# 02__RF_Power.net
KiCad netlist of a schematic drawn in Altium Designer
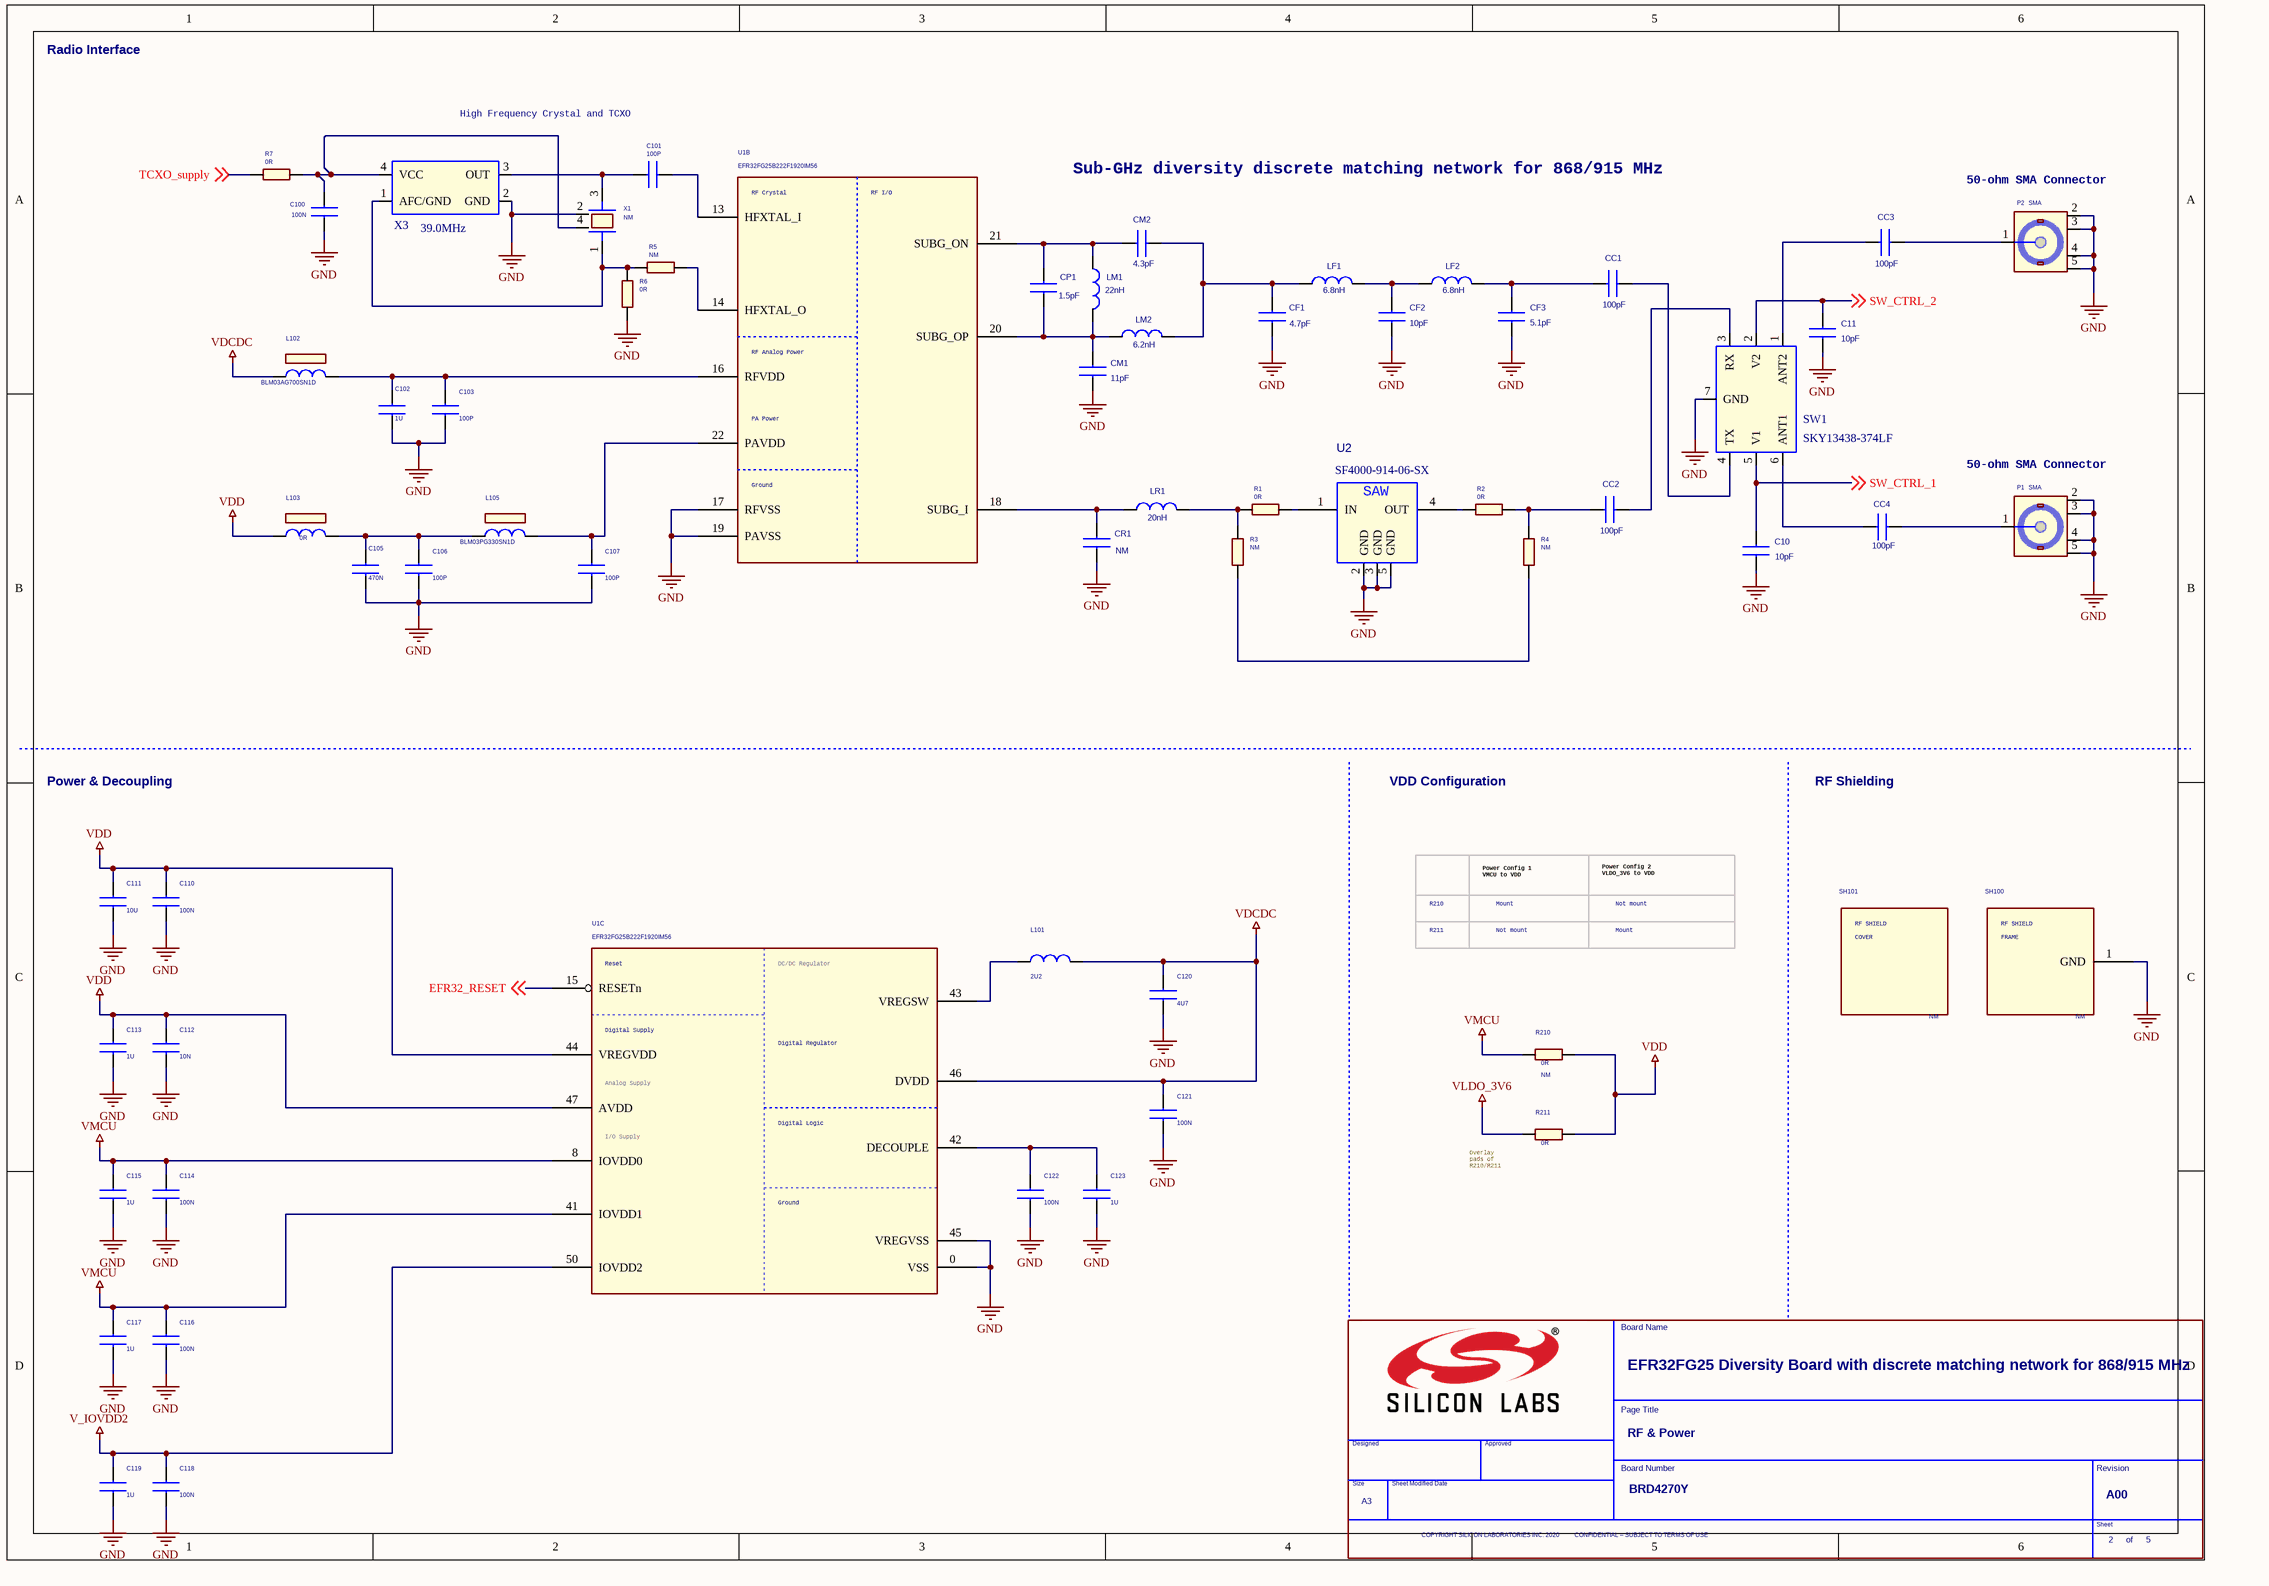
[diagram p0: 02_ RF & Power.SchDoc]

(export (version "E")
  (design (tool "Eeschema 10.0.6"))
  (components
    (comp (ref "C10")
      (value "10pF")
      (footprint "C0201_L")
      (fields (field (name "TOLERANCE") "±0.05P") (field (name "MFG") "Murata"))
      (libsource (lib "*") (part "C0201"))
    )
    (comp (ref "C11")
      (value "10pF")
      (footprint "C0201_L")
      (fields (field (name "TOLERANCE") "±0.05P") (field (name "MFG") "Murata"))
      (libsource (lib "*") (part "C0201"))
    )
    (comp (ref "C100")
      (value "100N")
      (footprint "C0201_L")
      (fields (field (name "TOLERANCE") "20%"))
      (libsource (lib "*") (part "C0201"))
    )
    (comp (ref "C101")
      (value "100P")
      (footprint "C0201_L")
      (fields (field (name "TOLERANCE") "5%"))
      (libsource (lib "*") (part "C0201"))
    )
    (comp (ref "C102")
      (value "1U")
      (footprint "C0402_L")
      (fields (field (name "TOLERANCE") "10%"))
      (libsource (lib "*") (part "C0402"))
    )
    (comp (ref "C103")
      (value "100P")
      (footprint "C0201_L")
      (fields (field (name "TOLERANCE") "5%"))
      (libsource (lib "*") (part "C0201"))
    )
    (comp (ref "C105")
      (value "470N")
      (footprint "C0402_L")
      (fields (field (name "TOLERANCE") "10%"))
      (libsource (lib "*") (part "C0402"))
    )
    (comp (ref "C106")
      (value "100P")
      (footprint "C0201_L")
      (fields (field (name "TOLERANCE") "5%"))
      (libsource (lib "*") (part "C0201"))
    )
    (comp (ref "C107")
      (value "100P")
      (footprint "C0201_L")
      (fields (field (name "TOLERANCE") "5%"))
      (libsource (lib "*") (part "C0201"))
    )
    (comp (ref "C110")
      (value "100N")
      (footprint "C0201_L")
      (fields (field (name "TOLERANCE") "20%"))
      (libsource (lib "*") (part "C0201"))
    )
    (comp (ref "C111")
      (value "10U")
      (footprint "C0603_L")
      (fields (field (name "TOLERANCE") "20%"))
      (libsource (lib "*") (part "C0603"))
    )
    (comp (ref "C112")
      (value "10N")
      (footprint "C0201_L")
      (fields (field (name "TOLERANCE") "10%"))
      (libsource (lib "*") (part "C0201"))
    )
    (comp (ref "C113")
      (value "1U")
      (footprint "C0402_L")
      (fields (field (name "TOLERANCE") "10%"))
      (libsource (lib "*") (part "C0402"))
    )
    (comp (ref "C114")
      (value "100N")
      (footprint "C0201_L")
      (fields (field (name "TOLERANCE") "20%"))
      (libsource (lib "*") (part "C0201"))
    )
    (comp (ref "C115")
      (value "1U")
      (footprint "C0402_L")
      (fields (field (name "TOLERANCE") "10%"))
      (libsource (lib "*") (part "C0402"))
    )
    (comp (ref "C116")
      (value "100N")
      (footprint "C0201_L")
      (fields (field (name "TOLERANCE") "20%"))
      (libsource (lib "*") (part "C0201"))
    )
    (comp (ref "C117")
      (value "1U")
      (footprint "C0402_L")
      (fields (field (name "TOLERANCE") "10%"))
      (libsource (lib "*") (part "C0402"))
    )
    (comp (ref "C118")
      (value "100N")
      (footprint "C0201_L")
      (fields (field (name "TOLERANCE") "20%"))
      (libsource (lib "*") (part "C0201"))
    )
    (comp (ref "C119")
      (value "1U")
      (footprint "C0402_L")
      (fields (field (name "TOLERANCE") "10%"))
      (libsource (lib "*") (part "C0402"))
    )
    (comp (ref "C120")
      (value "4U7")
      (footprint "C0603_L")
      (fields (field (name "TOLERANCE") "10%"))
      (libsource (lib "*") (part "C0603"))
    )
    (comp (ref "C121")
      (value "100N")
      (footprint "C0201_L")
      (fields (field (name "TOLERANCE") "20%"))
      (libsource (lib "*") (part "C0201"))
    )
    (comp (ref "C122")
      (value "100N")
      (footprint "C0201_L")
      (fields (field (name "TOLERANCE") "20%"))
      (libsource (lib "*") (part "C0201"))
    )
    (comp (ref "C123")
      (value "1U")
      (footprint "C0402_L")
      (fields (field (name "TOLERANCE") "10%"))
      (libsource (lib "*") (part "C0402"))
    )
    (comp (ref "CC1")
      (value "100pF")
      (footprint "C0201_L")
      (fields (field (name "TOLERANCE") "±0.05P") (field (name "MFG") "Murata"))
      (libsource (lib "*") (part "C0201"))
    )
    (comp (ref "CC2")
      (value "100pF")
      (footprint "C0201_L")
      (fields (field (name "TOLERANCE") "±0.05P") (field (name "MFG") "Murata"))
      (libsource (lib "*") (part "C0201"))
    )
    (comp (ref "CC3")
      (value "100pF")
      (footprint "C0201_L")
      (fields (field (name "TOLERANCE") "±0.05P") (field (name "MFG") "Murata"))
      (libsource (lib "*") (part "C0201"))
    )
    (comp (ref "CC4")
      (value "100pF")
      (footprint "C0201_L")
      (fields (field (name "TOLERANCE") "±0.05P") (field (name "MFG") "Murata"))
      (libsource (lib "*") (part "C0201"))
    )
    (comp (ref "CF1")
      (value "4.7pF")
      (footprint "C0201_L")
      (fields (field (name "TOLERANCE") "±0.1P") (field (name "MFG") "Murata"))
      (libsource (lib "*") (part "C0201"))
    )
    (comp (ref "CF2")
      (value "10pF")
      (footprint "C0201_L")
      (fields (field (name "TOLERANCE") "±0.1P") (field (name "MFG") "Murata"))
      (libsource (lib "*") (part "C0201"))
    )
    (comp (ref "CF3")
      (value "5.1pF")
      (footprint "C0201_L")
      (fields (field (name "TOLERANCE") "±0.05P") (field (name "MFG") "Murata"))
      (libsource (lib "*") (part "C0201"))
    )
    (comp (ref "CM1")
      (value "11pF")
      (footprint "C0201_L")
      (fields (field (name "TOLERANCE") "±0.1P") (field (name "MFG") "Murata"))
      (libsource (lib "*") (part "C0201"))
    )
    (comp (ref "CM2")
      (value "4.3pF")
      (footprint "C0201_L")
      (fields (field (name "TOLERANCE") "±0.05P") (field (name "MFG") "Murata"))
      (libsource (lib "*") (part "C0201"))
    )
    (comp (ref "CP1")
      (value "1.5pF")
      (footprint "C0201_L")
      (fields (field (name "TOLERANCE") "±0.1P") (field (name "MFG") "Murata"))
      (libsource (lib "*") (part "C0201"))
    )
    (comp (ref "CR1")
      (value "Unused")
      (footprint "C0201_L")
      (fields
        (field (name "TOLERANCE") "±0.05P")
        (field (name "NOT MOUNTED") "NM")
        (field (name "MFG") "Murata")
      )
      (libsource (lib "*") (part "C0201"))
    )
    (comp (ref "L101")
      (value "2U2")
      (footprint "COIL_1008_L")
      (fields (field (name "MFG") "Murata") (field (name "TOLERANCE") "+/-20%"))
      (libsource (lib "*") (part "L1008"))
    )
    (comp (ref "L102")
      (value "BLM03AG700SN1D")
      (footprint "COIL_MUR_BLM03_0201")
      (fields (field (name "MFG") "Murata"))
      (libsource (lib "*") (part "BLM03AX"))
    )
    (comp (ref "L103") (value "0R") (footprint "COIL_MUR_BLM03_0201") (libsource (lib "*") (part "BLM03AX")))
    (comp (ref "L105")
      (value "BLM03PG330SN1D")
      (footprint "COIL_MUR_BLM03_0201")
      (fields (field (name "MFG") "Murata"))
      (libsource (lib "*") (part "BLM03AX"))
    )
    (comp (ref "LF1")
      (value "6.8nH")
      (footprint "COIL_0201_L")
      (fields (field (name "TOLERANCE") "±3%") (field (name "MFG") "Murata"))
      (libsource (lib "*") (part "L0201"))
    )
    (comp (ref "LF2")
      (value "6.8nH")
      (footprint "COIL_0201_L")
      (fields (field (name "TOLERANCE") "±3%") (field (name "MFG") "Murata"))
      (libsource (lib "*") (part "L0201"))
    )
    (comp (ref "LM1")
      (value "22nH")
      (footprint "COIL_0201_L")
      (fields (field (name "TOLERANCE") "±0.1N") (field (name "MFG") "Murata"))
      (libsource (lib "*") (part "L0201"))
    )
    (comp (ref "LM2") (value "6.2nH") (footprint "COIL_0201_L") (libsource (lib "*") (part "L0201")))
    (comp (ref "LR1")
      (value "20nH")
      (footprint "COIL_0201_L")
      (fields (field (name "TOLERANCE") "±3%") (field (name "MFG") "Murata"))
      (libsource (lib "*") (part "L0201"))
    )
    (comp (ref "P1")
      (value "SMA")
      (footprint "TE_SMA_1814832_TH_VER")
      (fields (field (name "MFG") "Wellshow"))
      (libsource (lib "*") (part "SMA_TH_WELLSHOW"))
    )
    (comp (ref "P2")
      (value "SMA")
      (footprint "TE_SMA_1814832_TH_VER")
      (fields (field (name "MFG") "Wellshow"))
      (libsource (lib "*") (part "SMA_TH_WELLSHOW"))
    )
    (comp (ref "R1") (value "0R") (footprint "R0201_L") (libsource (lib "*") (part "R0201")))
    (comp (ref "R2") (value "0R") (footprint "R0201_L") (libsource (lib "*") (part "R0201")))
    (comp (ref "R3") (value "NM") (footprint "R0201_L") (libsource (lib "") (part "R0201_1")))
    (comp (ref "R4") (value "NM") (footprint "R0201_L") (libsource (lib "") (part "R0201_1")))
    (comp (ref "R5") (value "NM") (footprint "R0201_L") (libsource (lib "*") (part "R0201")))
    (comp (ref "R6") (value "0R") (footprint "R0201_L") (libsource (lib "") (part "R0201_1")))
    (comp (ref "R7") (value "0R") (footprint "R0201_L") (libsource (lib "*") (part "R0201")))
    (comp (ref "R210")
      (value "0R")
      (footprint "R0402_L")
      (fields (field (name "NOT MOUNTED") "NM"))
      (libsource (lib "*") (part "R0402"))
    )
    (comp (ref "R211") (value "0R") (footprint "R0402_L") (libsource (lib "*") (part "R0402")))
    (comp (ref "SH100")
      (value "RF_SHIELD_FRAME_BMI-S-203-F")
      (footprint "LAIRD_BMI-S-203-F")
      (fields (field (name "NOT MOUNTED") "NM") (field (name "MFG") "Laird Technologies"))
      (libsource (lib "*") (part "RF_SHIELD_FRAME_BMI-S-203-F"))
    )
    (comp (ref "SH101")
      (value "RF_SHIELD_COVER_BMI-S-203-C")
      (fields (field (name "MFG") "Laird Technologies") (field (name "NOT MOUNTED") "NM"))
      (libsource (lib "*") (part "RF_SHIELD_COVER_BMI-S-203-C"))
    )
    (comp (ref "SW1")
      (value "SKY13438-374LF")
      (footprint "SKY13438-374LF_footprint")
      (fields (field (name "MFG") "Infineon"))
      (libsource (lib "BRD4270Y_Library") (part "Switch DPDT"))
    )
    (comp (ref "U1")
      (value "EFR32FG25B222F1920IM56")
      (footprint "QFN56_M040_7.0X7.0_EP_SL")
      (fields (field (name "MFG") "Silicon Labs"))
      (libsource (lib "*") (part "EFR32xG25_QFN56_HFCLKOUT"))
    )
    (comp (ref "U2")
      (value "SF4000-914-06-SX")
      (footprint "SF1256")
      (description "B2645 from Qualcomm also fits")
      (fields (field (name "MFG") "ACTE"))
      (libsource (lib "BRD4270Y_Library") (part "SF4000-914-06-SX"))
    )
    (comp (ref "X1")
      (value "NM")
      (footprint "X_SSS_DSX211SH_2.05X1.65-4")
      (fields (field (name "MFG") "Tai-Saw"))
      (libsource (lib "*") (part "DSX211SH"))
    )
    (comp (ref "X3")
      (value "39.0MHz")
      (footprint "TCXO TX0862AAAM53_SMD2016")
      (fields (field (name "MFG") "TXC"))
      (libsource (lib "BRD4270Y_Library") (part "TCXO TX0862AAAM53"))
    )
  )
  (nets
    (net (code "1") (name "EFR32_RESET") (class "Default")
      (node (ref "U1") (pin "15") (pinfunction "RESETn_15") (pintype "passive"))
    )
    (net (code "2") (name "GND") (class "Default")
      (node (ref "C10") (pin "2") (pinfunction "2_2") (pintype "passive"))
      (node (ref "C100") (pin "2") (pinfunction "2_2") (pintype "passive"))
      (node (ref "C102") (pin "2") (pinfunction "2_2") (pintype "passive"))
      (node (ref "C103") (pin "2") (pinfunction "2_2") (pintype "passive"))
      (node (ref "C105") (pin "2") (pinfunction "2_2") (pintype "passive"))
      (node (ref "C106") (pin "2") (pinfunction "2_2") (pintype "passive"))
      (node (ref "C107") (pin "2") (pinfunction "2_2") (pintype "passive"))
      (node (ref "C11") (pin "2") (pinfunction "2_2") (pintype "passive"))
      (node (ref "C110") (pin "2") (pinfunction "2_2") (pintype "passive"))
      (node (ref "C111") (pin "2") (pinfunction "2_2") (pintype "passive"))
      (node (ref "C112") (pin "2") (pinfunction "2_2") (pintype "passive"))
      (node (ref "C113") (pin "2") (pinfunction "2_2") (pintype "passive"))
      (node (ref "C114") (pin "2") (pinfunction "2_2") (pintype "passive"))
      (node (ref "C115") (pin "2") (pinfunction "2_2") (pintype "passive"))
      (node (ref "C116") (pin "2") (pinfunction "2_2") (pintype "passive"))
      (node (ref "C117") (pin "2") (pinfunction "2_2") (pintype "passive"))
      (node (ref "C118") (pin "2") (pinfunction "2_2") (pintype "passive"))
      (node (ref "C119") (pin "2") (pinfunction "2_2") (pintype "passive"))
      (node (ref "C120") (pin "2") (pinfunction "2_2") (pintype "passive"))
      (node (ref "C121") (pin "2") (pinfunction "2_2") (pintype "passive"))
      (node (ref "C122") (pin "2") (pinfunction "2_2") (pintype "passive"))
      (node (ref "C123") (pin "2") (pinfunction "2_2") (pintype "passive"))
      (node (ref "CF1") (pin "2") (pinfunction "2_2") (pintype "passive"))
      (node (ref "CF2") (pin "2") (pinfunction "2_2") (pintype "passive"))
      (node (ref "CF3") (pin "2") (pinfunction "2_2") (pintype "passive"))
      (node (ref "CM1") (pin "2") (pinfunction "2_2") (pintype "passive"))
      (node (ref "CR1") (pin "2") (pinfunction "2_2") (pintype "passive"))
      (node (ref "P1") (pin "2") (pinfunction "GND1_2") (pintype "passive"))
      (node (ref "P1") (pin "3") (pinfunction "GND2_3") (pintype "passive"))
      (node (ref "P1") (pin "4") (pinfunction "GND3_4") (pintype "passive"))
      (node (ref "P1") (pin "5") (pinfunction "GND4_5") (pintype "passive"))
      (node (ref "P2") (pin "2") (pinfunction "GND1_2") (pintype "passive"))
      (node (ref "P2") (pin "3") (pinfunction "GND2_3") (pintype "passive"))
      (node (ref "P2") (pin "4") (pinfunction "GND3_4") (pintype "passive"))
      (node (ref "P2") (pin "5") (pinfunction "GND4_5") (pintype "passive"))
      (node (ref "R6") (pin "1") (pinfunction "1_1") (pintype "passive"))
      (node (ref "SH100") (pin "1") (pinfunction "GND_1") (pintype "passive"))
      (node (ref "SW1") (pin "7") (pinfunction "GND_7") (pintype "passive"))
      (node (ref "U1") (pin "0") (pinfunction "VSS_0") (pintype "power_in"))
      (node (ref "U1") (pin "17") (pinfunction "RFVSS_17") (pintype "passive"))
      (node (ref "U1") (pin "19") (pinfunction "PAVSS_19") (pintype "passive"))
      (node (ref "U1") (pin "45") (pinfunction "VREGVSS_45") (pintype "passive"))
      (node (ref "U2") (pin "2") (pinfunction "GND_2") (pintype "passive"))
      (node (ref "U2") (pin "3") (pinfunction "GND_3") (pintype "passive"))
      (node (ref "U2") (pin "5") (pinfunction "GND_5") (pintype "passive"))
      (node (ref "X1") (pin "2") (pinfunction "2_2") (pintype "passive"))
      (node (ref "X3") (pin "2") (pinfunction "GND_2") (pintype "passive"))
    )
    (net (code "3") (name "Net-(C105-Pad1)") (class "Default")
      (node (ref "C105") (pin "1") (pinfunction "1_1") (pintype "passive"))
      (node (ref "C106") (pin "1") (pinfunction "1_1") (pintype "passive"))
      (node (ref "L103") (pin "2") (pinfunction "2_2") (pintype "passive"))
      (node (ref "L105") (pin "1") (pinfunction "1_1") (pintype "passive"))
    )
    (net (code "4") (name "Net-(CC1-Pad1)") (class "Default")
      (node (ref "CC1") (pin "1") (pinfunction "1_1") (pintype "passive"))
      (node (ref "CF3") (pin "1") (pinfunction "1_1") (pintype "passive"))
      (node (ref "LF2") (pin "2") (pinfunction "2_2") (pintype "passive"))
    )
    (net (code "5") (name "Net-(CC2-Pad1)") (class "Default")
      (node (ref "CC2") (pin "1") (pinfunction "1_1") (pintype "passive"))
      (node (ref "R2") (pin "2") (pinfunction "2_2") (pintype "passive"))
      (node (ref "R4") (pin "2") (pinfunction "2_2") (pintype "passive"))
    )
    (net (code "6") (name "Net-(CF1-Pad1)") (class "Default")
      (node (ref "CF1") (pin "1") (pinfunction "1_1") (pintype "passive"))
      (node (ref "CM2") (pin "2") (pinfunction "2_2") (pintype "passive"))
      (node (ref "LF1") (pin "1") (pinfunction "1_1") (pintype "passive"))
      (node (ref "LM2") (pin "2") (pinfunction "2_2") (pintype "passive"))
    )
    (net (code "7") (name "Net-(CF2-Pad1)") (class "Default")
      (node (ref "CF2") (pin "1") (pinfunction "1_1") (pintype "passive"))
      (node (ref "LF1") (pin "2") (pinfunction "2_2") (pintype "passive"))
      (node (ref "LF2") (pin "1") (pinfunction "1_1") (pintype "passive"))
    )
    (net (code "8") (name "Net-(LR1-Pad2)") (class "Default")
      (node (ref "LR1") (pin "2") (pinfunction "2_2") (pintype "passive"))
      (node (ref "R1") (pin "1") (pinfunction "1_1") (pintype "passive"))
      (node (ref "R3") (pin "2") (pinfunction "2_2") (pintype "passive"))
    )
    (net (code "9") (name "Net-(P1-SIGNAL)") (class "Default")
      (node (ref "CC4") (pin "2") (pinfunction "2_2") (pintype "passive"))
      (node (ref "P1") (pin "1") (pinfunction "SIGNAL_1") (pintype "passive"))
    )
    (net (code "10") (name "Net-(P2-SIGNAL)") (class "Default")
      (node (ref "CC3") (pin "2") (pinfunction "2_2") (pintype "passive"))
      (node (ref "P2") (pin "1") (pinfunction "SIGNAL_1") (pintype "passive"))
    )
    (net (code "11") (name "Net-(R3-Pad1)") (class "Default")
      (node (ref "R3") (pin "1") (pinfunction "1_1") (pintype "passive"))
      (node (ref "R4") (pin "1") (pinfunction "1_1") (pintype "passive"))
    )
    (net (code "12") (name "Net-(SW1-ANT1)") (class "Default")
      (node (ref "CC4") (pin "1") (pinfunction "1_1") (pintype "passive"))
      (node (ref "SW1") (pin "6") (pinfunction "ANT1_6") (pintype "passive"))
    )
    (net (code "13") (name "Net-(SW1-ANT2)") (class "Default")
      (node (ref "CC3") (pin "1") (pinfunction "1_1") (pintype "passive"))
      (node (ref "SW1") (pin "1") (pinfunction "ANT2_1") (pintype "passive"))
    )
    (net (code "14") (name "Net-(SW1-RX)") (class "Default")
      (node (ref "CC2") (pin "2") (pinfunction "2_2") (pintype "passive"))
      (node (ref "SW1") (pin "3") (pinfunction "RX_3") (pintype "passive"))
    )
    (net (code "15") (name "Net-(SW1-TX)") (class "Default")
      (node (ref "CC1") (pin "2") (pinfunction "2_2") (pintype "passive"))
      (node (ref "SW1") (pin "4") (pinfunction "TX_4") (pintype "passive"))
    )
    (net (code "16") (name "Net-(U1B-HFXTAL_I)") (class "Default")
      (node (ref "C101") (pin "2") (pinfunction "2_2") (pintype "passive"))
      (node (ref "U1") (pin "13") (pinfunction "HFXTAL_I_13") (pintype "passive"))
    )
    (net (code "17") (name "Net-(U1B-HFXTAL_O)") (class "Default")
      (node (ref "R5") (pin "2") (pinfunction "2_2") (pintype "passive"))
      (node (ref "U1") (pin "14") (pinfunction "HFXTAL_O_14") (pintype "passive"))
    )
    (net (code "18") (name "Net-(U1B-PAVDD)") (class "Default")
      (node (ref "C107") (pin "1") (pinfunction "1_1") (pintype "passive"))
      (node (ref "L105") (pin "2") (pinfunction "2_2") (pintype "passive"))
      (node (ref "U1") (pin "22") (pinfunction "PAVDD_22") (pintype "passive"))
    )
    (net (code "19") (name "Net-(U1B-RFVDD)") (class "Default")
      (node (ref "C102") (pin "1") (pinfunction "1_1") (pintype "passive"))
      (node (ref "C103") (pin "1") (pinfunction "1_1") (pintype "passive"))
      (node (ref "L102") (pin "2") (pinfunction "2_2") (pintype "passive"))
      (node (ref "U1") (pin "16") (pinfunction "RFVDD_16") (pintype "power_in"))
    )
    (net (code "20") (name "Net-(U1B-SUBG_I)") (class "Default")
      (node (ref "CR1") (pin "1") (pinfunction "1_1") (pintype "passive"))
      (node (ref "LR1") (pin "1") (pinfunction "1_1") (pintype "passive"))
      (node (ref "U1") (pin "18") (pinfunction "SUBG_I_18") (pintype "passive"))
    )
    (net (code "21") (name "Net-(U1B-SUBG_ON)") (class "Default")
      (node (ref "CM2") (pin "1") (pinfunction "1_1") (pintype "passive"))
      (node (ref "CP1") (pin "1") (pinfunction "1_1") (pintype "passive"))
      (node (ref "LM1") (pin "1") (pinfunction "1_1") (pintype "passive"))
      (node (ref "U1") (pin "21") (pinfunction "SUBG_ON_21") (pintype "passive"))
    )
    (net (code "22") (name "Net-(U1B-SUBG_OP)") (class "Default")
      (node (ref "CM1") (pin "1") (pinfunction "1_1") (pintype "passive"))
      (node (ref "CP1") (pin "2") (pinfunction "2_2") (pintype "passive"))
      (node (ref "LM1") (pin "2") (pinfunction "2_2") (pintype "passive"))
      (node (ref "LM2") (pin "1") (pinfunction "1_1") (pintype "passive"))
      (node (ref "U1") (pin "20") (pinfunction "SUBG_OP_20") (pintype "passive"))
    )
    (net (code "23") (name "Net-(U1C-DECOUPLE)") (class "Default")
      (node (ref "C122") (pin "1") (pinfunction "1_1") (pintype "passive"))
      (node (ref "C123") (pin "1") (pinfunction "1_1") (pintype "passive"))
      (node (ref "U1") (pin "42") (pinfunction "DECOUPLE_42") (pintype "power_in"))
    )
    (net (code "24") (name "Net-(U1C-VREGSW)") (class "Default")
      (node (ref "L101") (pin "1") (pinfunction "1_1") (pintype "passive"))
      (node (ref "U1") (pin "43") (pinfunction "VREGSW_43") (pintype "passive"))
    )
    (net (code "25") (name "Net-(U2-IN)") (class "Default")
      (node (ref "R1") (pin "2") (pinfunction "2_2") (pintype "passive"))
      (node (ref "U2") (pin "1") (pinfunction "IN_1") (pintype "passive"))
    )
    (net (code "26") (name "Net-(U2-OUT)") (class "Default")
      (node (ref "R2") (pin "1") (pinfunction "1_1") (pintype "passive"))
      (node (ref "U2") (pin "4") (pinfunction "OUT_4") (pintype "passive"))
    )
    (net (code "27") (name "Net-(X3-AFC{slash}GND)") (class "Default")
      (node (ref "R5") (pin "1") (pinfunction "1_1") (pintype "passive"))
      (node (ref "R6") (pin "2") (pinfunction "2_2") (pintype "passive"))
      (node (ref "X1") (pin "1") (pinfunction "1_1") (pintype "passive"))
      (node (ref "X3") (pin "1") (pinfunction "AFC/GND_1") (pintype "passive"))
    )
    (net (code "28") (name "Net-(X3-OUT)") (class "Default")
      (node (ref "C101") (pin "1") (pinfunction "1_1") (pintype "passive"))
      (node (ref "X1") (pin "3") (pinfunction "3_3") (pintype "passive"))
      (node (ref "X3") (pin "3") (pinfunction "OUT_3") (pintype "passive"))
    )
    (net (code "29") (name "Net-(X3-VCC)") (class "Default")
      (node (ref "C100") (pin "1") (pinfunction "1_1") (pintype "passive"))
      (node (ref "R7") (pin "2") (pinfunction "2_2") (pintype "passive"))
      (node (ref "X1") (pin "4") (pinfunction "4_4") (pintype "passive"))
      (node (ref "X3") (pin "4") (pinfunction "VCC_4") (pintype "passive"))
    )
    (net (code "30") (name "SW_CTRL_1") (class "Default")
      (node (ref "C10") (pin "1") (pinfunction "1_1") (pintype "passive"))
      (node (ref "SW1") (pin "5") (pinfunction "V1_5") (pintype "passive"))
    )
    (net (code "31") (name "SW_CTRL_2") (class "Default")
      (node (ref "C11") (pin "1") (pinfunction "1_1") (pintype "passive"))
      (node (ref "SW1") (pin "2") (pinfunction "V2_2") (pintype "passive"))
    )
    (net (code "32") (name "TCXO_supply") (class "Default")
      (node (ref "R7") (pin "1") (pinfunction "1_1") (pintype "passive"))
    )
    (net (code "33") (name "VDCDC") (class "Default")
      (node (ref "C120") (pin "1") (pinfunction "1_1") (pintype "passive"))
      (node (ref "C121") (pin "1") (pinfunction "1_1") (pintype "passive"))
      (node (ref "L101") (pin "2") (pinfunction "2_2") (pintype "passive"))
      (node (ref "L102") (pin "1") (pinfunction "1_1") (pintype "passive"))
      (node (ref "U1") (pin "46") (pinfunction "DVDD_46") (pintype "power_in"))
    )
    (net (code "34") (name "VDD") (class "Default")
      (node (ref "C110") (pin "1") (pinfunction "1_1") (pintype "passive"))
      (node (ref "C111") (pin "1") (pinfunction "1_1") (pintype "passive"))
      (node (ref "C112") (pin "1") (pinfunction "1_1") (pintype "passive"))
      (node (ref "C113") (pin "1") (pinfunction "1_1") (pintype "passive"))
      (node (ref "L103") (pin "1") (pinfunction "1_1") (pintype "passive"))
      (node (ref "R210") (pin "2") (pinfunction "2_2") (pintype "passive"))
      (node (ref "R211") (pin "2") (pinfunction "2_2") (pintype "passive"))
      (node (ref "U1") (pin "44") (pinfunction "VREGVDD_44") (pintype "passive"))
      (node (ref "U1") (pin "47") (pinfunction "AVDD_47") (pintype "power_in"))
    )
    (net (code "35") (name "VLDO_3V6") (class "Default")
      (node (ref "R211") (pin "1") (pinfunction "1_1") (pintype "passive"))
    )
    (net (code "36") (name "VMCU") (class "Default")
      (node (ref "C114") (pin "1") (pinfunction "1_1") (pintype "passive"))
      (node (ref "C115") (pin "1") (pinfunction "1_1") (pintype "passive"))
      (node (ref "C116") (pin "1") (pinfunction "1_1") (pintype "passive"))
      (node (ref "C117") (pin "1") (pinfunction "1_1") (pintype "passive"))
      (node (ref "R210") (pin "1") (pinfunction "1_1") (pintype "passive"))
      (node (ref "U1") (pin "41") (pinfunction "IOVDD1_41") (pintype "power_in"))
      (node (ref "U1") (pin "8") (pinfunction "IOVDD0_8") (pintype "power_in"))
    )
    (net (code "37") (name "V_IOVDD2") (class "Default")
      (node (ref "C118") (pin "1") (pinfunction "1_1") (pintype "passive"))
      (node (ref "C119") (pin "1") (pinfunction "1_1") (pintype "passive"))
      (node (ref "U1") (pin "50") (pinfunction "IOVDD2_50") (pintype "power_in"))
    )
  )
)
